# TLC6C598_Q1.net
KiCad netlist of a schematic drawn in Altium Designer
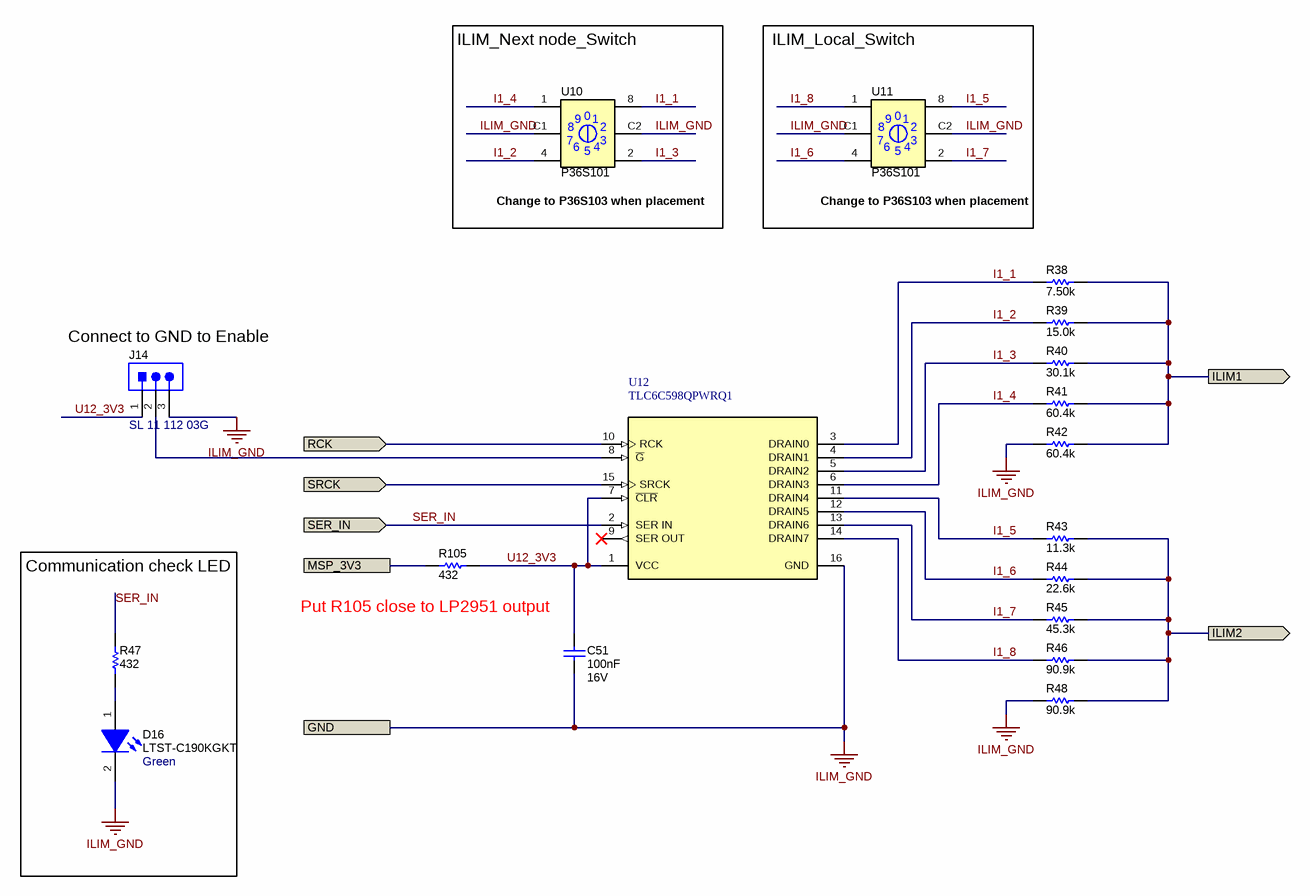
[diagram p0: TLC6C598_Q1.SchDoc]

(export (version "E")
  (design (tool "Eeschema 10.0.6"))
  (components
    (comp (ref "C51")
      (value "GRM188R71C104KA01D")
      (footprint "0603")
      (description "CAP, CERM, 0.1 uF, 16 V, +/- 10%, X7R, 0603")
      (fields
        (field (name "MANUFACTURER") "MuRata")
        (field (name "CAP_F") "100nF")
        (field (name "VDC_V") "16V")
        (field (name "PUBLISHER") "Texas Instruments")
      )
      (libsource (lib "Altium Vault - TI") (part "Capacitor"))
    )
    (comp (ref "D16")
      (value "LTST-C190KGKT")
      (footprint "LED_LTST-C190_G")
      (description "LED, Green, SMD")
      (fields (field (name "ALTIUM_VALUE") "Green") (field (name "MANUFACTURER") "Lite-On"))
      (libsource (lib "Altium Vault - TI") (part "LED"))
    )
    (comp (ref "J14")
      (value "SL 11 112 03G")
      (footprint "Fischer_SL-11-112-03G")
      (description "Header, 2.54mm, 3x1, Gold, TH")
      (fields
        (field (name "MANUFACTURER") "Fischer Elektronik")
        (field (name "PUBLISHER") "Texas Instruments")
      )
      (libsource (lib "Altium Vault - TI") (part "Header_3x1"))
    )
    (comp (ref "R38")
      (value "CRCW04027K50FKED")
      (footprint "0402")
      (description "RES, 7.50 k, 1%, 0.063 W, AEC-Q200 Grade 0, 0402")
      (fields (field (name "MANUFACTURER") "Vishay-Dale") (field (name "VALUEDISPLAYED") "7.50k"))
      (libsource (lib "Altium Vault - TI") (part "Resistor"))
    )
    (comp (ref "R39")
      (value "CRCW040215K0FKED")
      (footprint "0402")
      (description "RES, 15.0 k, 1%, 0.063 W, AEC-Q200 Grade 0, 0402")
      (fields (field (name "MANUFACTURER") "Vishay-Dale") (field (name "VALUEDISPLAYED") "15.0k"))
      (libsource (lib "Altium Vault - TI") (part "Resistor"))
    )
    (comp (ref "R40")
      (value "CRCW040230K1FKED")
      (footprint "0402")
      (description "RES, 30.1 k, 1%, 0.063 W, AEC-Q200 Grade 0, 0402")
      (fields (field (name "MANUFACTURER") "Vishay-Dale") (field (name "VALUEDISPLAYED") "30.1k"))
      (libsource (lib "Altium Vault - TI") (part "Resistor"))
    )
    (comp (ref "R41")
      (value "CRCW040260K4FKED")
      (footprint "0402")
      (description "RES, 60.4 k, 1%, 0.063 W, AEC-Q200 Grade 0, 0402")
      (fields (field (name "MANUFACTURER") "Vishay-Dale") (field (name "VALUEDISPLAYED") "60.4k"))
      (libsource (lib "Altium Vault - TI") (part "Resistor"))
    )
    (comp (ref "R42")
      (value "CRCW040260K4FKED")
      (footprint "0402")
      (description "RES, 60.4 k, 1%, 0.063 W, AEC-Q200 Grade 0, 0402")
      (fields (field (name "MANUFACTURER") "Vishay-Dale") (field (name "VALUEDISPLAYED") "60.4k"))
      (libsource (lib "Altium Vault - TI") (part "Resistor"))
    )
    (comp (ref "R43")
      (value "CRCW040211K3FKED")
      (footprint "0402")
      (description "RES, 11.3 k, 1%, 0.063 W, AEC-Q200 Grade 0, 0402")
      (fields (field (name "MANUFACTURER") "Vishay-Dale") (field (name "VALUEDISPLAYED") "11.3k"))
      (libsource (lib "Altium Vault - TI") (part "Resistor"))
    )
    (comp (ref "R44")
      (value "CRCW040222K6FKED")
      (footprint "0402")
      (description "RES, 22.6 k, 1%, 0.063 W, AEC-Q200 Grade 0, 0402")
      (fields (field (name "MANUFACTURER") "Vishay-Dale") (field (name "VALUEDISPLAYED") "22.6k"))
      (libsource (lib "Altium Vault - TI") (part "Resistor"))
    )
    (comp (ref "R45")
      (value "CRCW040245K3FKED")
      (footprint "0402")
      (description "RES, 45.3 k, 1%, 0.063 W, AEC-Q200 Grade 0, 0402")
      (fields (field (name "MANUFACTURER") "Vishay-Dale") (field (name "VALUEDISPLAYED") "45.3k"))
      (libsource (lib "Altium Vault - TI") (part "Resistor"))
    )
    (comp (ref "R46")
      (value "CRCW040290K9FKED")
      (footprint "0402")
      (description "RES, 90.9 k, 1%, 0.063 W, AEC-Q200 Grade 0, 0402")
      (fields (field (name "MANUFACTURER") "Vishay-Dale") (field (name "VALUEDISPLAYED") "90.9k"))
      (libsource (lib "Altium Vault - TI") (part "Resistor"))
    )
    (comp (ref "R47")
      (value "CRCW0603432RFKEA")
      (footprint "0603")
      (description "RES, 432, 1%, 0.1 W, AEC-Q200 Grade 0, 0603")
      (fields (field (name "MANUFACTURER") "Vishay-Dale") (field (name "VALUEDISPLAYED") "432"))
      (libsource (lib "Altium Vault - TI") (part "Resistor"))
    )
    (comp (ref "R48")
      (value "CRCW040290K9FKED")
      (footprint "0402")
      (description "RES, 90.9 k, 1%, 0.063 W, AEC-Q200 Grade 0, 0402")
      (fields (field (name "MANUFACTURER") "Vishay-Dale") (field (name "VALUEDISPLAYED") "90.9k"))
      (libsource (lib "Altium Vault - TI") (part "Resistor"))
    )
    (comp (ref "R105")
      (value "CRCW0603432RFKEA")
      (footprint "0603")
      (description "RES, 432, 1%, 0.1 W, AEC-Q200 Grade 0, 0603")
      (fields (field (name "MANUFACTURER") "Vishay-Dale") (field (name "VALUEDISPLAYED") "432"))
      (libsource (lib "Altium Vault - TI") (part "Resistor"))
    )
    (comp (ref "U10")
      (value "P36S101")
      (footprint "Apem_P36S10x")
      (description "Switch, Rotary dip, 10POS, BCD, 24V, SMT")
      (fields (field (name "MANUFACTURER") "APEM") (field (name "PUBLISHER") "Texas Instruments"))
      (libsource (lib "Altium Vault - TI") (part "SW_BCD_P36"))
    )
    (comp (ref "U11")
      (value "P36S101")
      (footprint "Apem_P36S10x")
      (description "Switch, Rotary dip, 10POS, BCD, 24V, SMT")
      (fields (field (name "MANUFACTURER") "APEM") (field (name "PUBLISHER") "Texas Instruments"))
      (libsource (lib "Altium Vault - TI") (part "SW_BCD_P36"))
    )
    (comp (ref "U12")
      (value "TLC6C598QPWRQ1")
      (footprint "PW0016A_N")
      (description "Automotive Power Logic 8-Bit Shift Register LED Driver, PW0016A, LARGE T&R")
      (fields
        (field (name "GENERIC PART NUMBER") "TLC6C598-Q1")
        (field (name "MANUFACTURER") "Texas Instruments")
      )
      (libsource (lib "Altium Vault - TI") (part "TI-TLC6C598-Q1-16"))
    )
  )
  (nets
    (net (code "1") (name "/I1_1") (class "Default")
      (node (ref "R38") (pin "1") (pinfunction "1_1") (pintype "passive"))
      (node (ref "U10") (pin "8") (pintype "passive"))
      (node (ref "U12") (pin "3") (pinfunction "DRAIN0_3") (pintype "open_collector"))
    )
    (net (code "2") (name "/I1_2") (class "Default")
      (node (ref "R39") (pin "1") (pinfunction "1_1") (pintype "passive"))
      (node (ref "U10") (pin "4") (pintype "passive"))
      (node (ref "U12") (pin "4") (pinfunction "DRAIN1_4") (pintype "open_collector"))
    )
    (net (code "3") (name "/I1_3") (class "Default")
      (node (ref "R40") (pin "1") (pinfunction "1_1") (pintype "passive"))
      (node (ref "U10") (pin "2") (pinfunction "2_2") (pintype "passive"))
      (node (ref "U12") (pin "5") (pinfunction "DRAIN2_5") (pintype "open_collector"))
    )
    (net (code "4") (name "/I1_4") (class "Default")
      (node (ref "R41") (pin "1") (pinfunction "1_1") (pintype "passive"))
      (node (ref "U10") (pin "1") (pinfunction "1_1") (pintype "passive"))
      (node (ref "U12") (pin "6") (pinfunction "DRAIN3_6") (pintype "open_collector"))
    )
    (net (code "5") (name "/I1_5") (class "Default")
      (node (ref "R43") (pin "1") (pinfunction "1_1") (pintype "passive"))
      (node (ref "U11") (pin "8") (pintype "passive"))
      (node (ref "U12") (pin "11") (pinfunction "DRAIN4_11") (pintype "open_collector"))
    )
    (net (code "6") (name "/I1_6") (class "Default")
      (node (ref "R44") (pin "1") (pinfunction "1_1") (pintype "passive"))
      (node (ref "U11") (pin "4") (pintype "passive"))
      (node (ref "U12") (pin "12") (pinfunction "DRAIN5_12") (pintype "open_collector"))
    )
    (net (code "7") (name "/I1_7") (class "Default")
      (node (ref "R45") (pin "1") (pinfunction "1_1") (pintype "passive"))
      (node (ref "U11") (pin "2") (pinfunction "2_2") (pintype "passive"))
      (node (ref "U12") (pin "13") (pinfunction "DRAIN6_13") (pintype "open_collector"))
    )
    (net (code "8") (name "/I1_8") (class "Default")
      (node (ref "R46") (pin "1") (pinfunction "1_1") (pintype "passive"))
      (node (ref "U11") (pin "1") (pinfunction "1_1") (pintype "passive"))
      (node (ref "U12") (pin "14") (pinfunction "DRAIN7_14") (pintype "open_collector"))
    )
    (net (code "9") (name "/ILIM1") (class "Default")
      (node (ref "R38") (pin "2") (pinfunction "2_2") (pintype "passive"))
      (node (ref "R39") (pin "2") (pinfunction "2_2") (pintype "passive"))
      (node (ref "R40") (pin "2") (pinfunction "2_2") (pintype "passive"))
      (node (ref "R41") (pin "2") (pinfunction "2_2") (pintype "passive"))
      (node (ref "R42") (pin "2") (pinfunction "2_2") (pintype "passive"))
    )
    (net (code "10") (name "/ILIM2") (class "Default")
      (node (ref "R43") (pin "2") (pinfunction "2_2") (pintype "passive"))
      (node (ref "R44") (pin "2") (pinfunction "2_2") (pintype "passive"))
      (node (ref "R45") (pin "2") (pinfunction "2_2") (pintype "passive"))
      (node (ref "R46") (pin "2") (pinfunction "2_2") (pintype "passive"))
      (node (ref "R48") (pin "2") (pinfunction "2_2") (pintype "passive"))
    )
    (net (code "11") (name "/MSP_3V3") (class "Default")
      (node (ref "R105") (pin "2") (pinfunction "2_2") (pintype "passive"))
    )
    (net (code "12") (name "/RCK") (class "Default")
      (node (ref "U12") (pin "10") (pinfunction "RCK_10") (pintype "input"))
    )
    (net (code "13") (name "/SER_IN") (class "Default")
      (node (ref "R47") (pin "2") (pinfunction "2_2") (pintype "passive"))
      (node (ref "U12") (pin "2") (pinfunction "SER_IN_2") (pintype "input"))
    )
    (net (code "14") (name "/SRCK") (class "Default")
      (node (ref "U12") (pin "15") (pinfunction "SRCK_15") (pintype "input"))
    )
    (net (code "15") (name "/U12_3V3") (class "Default")
      (node (ref "C51") (pin "1") (pinfunction "1_1") (pintype "passive"))
      (node (ref "J14") (pin "1") (pinfunction "1_1") (pintype "passive"))
      (node (ref "R105") (pin "1") (pinfunction "1_1") (pintype "passive"))
      (node (ref "U12") (pin "1") (pinfunction "VCC_1") (pintype "power_in"))
      (node (ref "U12") (pin "7") (pinfunction "~{CLR}_7") (pintype "input"))
    )
    (net (code "16") (name "ILIM_GND") (class "Default")
      (node (ref "C51") (pin "2") (pinfunction "2_2") (pintype "passive"))
      (node (ref "D16") (pin "2") (pinfunction "K_2") (pintype "passive"))
      (node (ref "J14") (pin "3") (pinfunction "3_3") (pintype "passive"))
      (node (ref "R42") (pin "1") (pinfunction "1_1") (pintype "passive"))
      (node (ref "R48") (pin "1") (pinfunction "1_1") (pintype "passive"))
      (node (ref "U10") (pin "C1") (pintype "passive"))
      (node (ref "U10") (pin "C2") (pintype "passive"))
      (node (ref "U11") (pin "C1") (pintype "passive"))
      (node (ref "U11") (pin "C2") (pintype "passive"))
      (node (ref "U12") (pin "16") (pinfunction "GND_16") (pintype "power_in"))
    )
    (net (code "17") (name "Net-(D16-A)") (class "Default")
      (node (ref "D16") (pin "1") (pinfunction "A_1") (pintype "passive"))
      (node (ref "R47") (pin "1") (pinfunction "1_1") (pintype "passive"))
    )
    (net (code "18") (name "Net-(U12-~{G})") (class "Default")
      (node (ref "J14") (pin "2") (pinfunction "2_2") (pintype "passive"))
      (node (ref "U12") (pin "8") (pinfunction "~{G}_8") (pintype "input"))
    )
    (net (code "19") (name "unconnected-(U12-SER_OUT-Pad9)") (class "Default")
      (node (ref "U12") (pin "9") (pinfunction "SER_OUT_9") (pintype "output+no_connect"))
    )
  )
)
